# communication.net
KiCad netlist of a schematic drawn in EAGLE
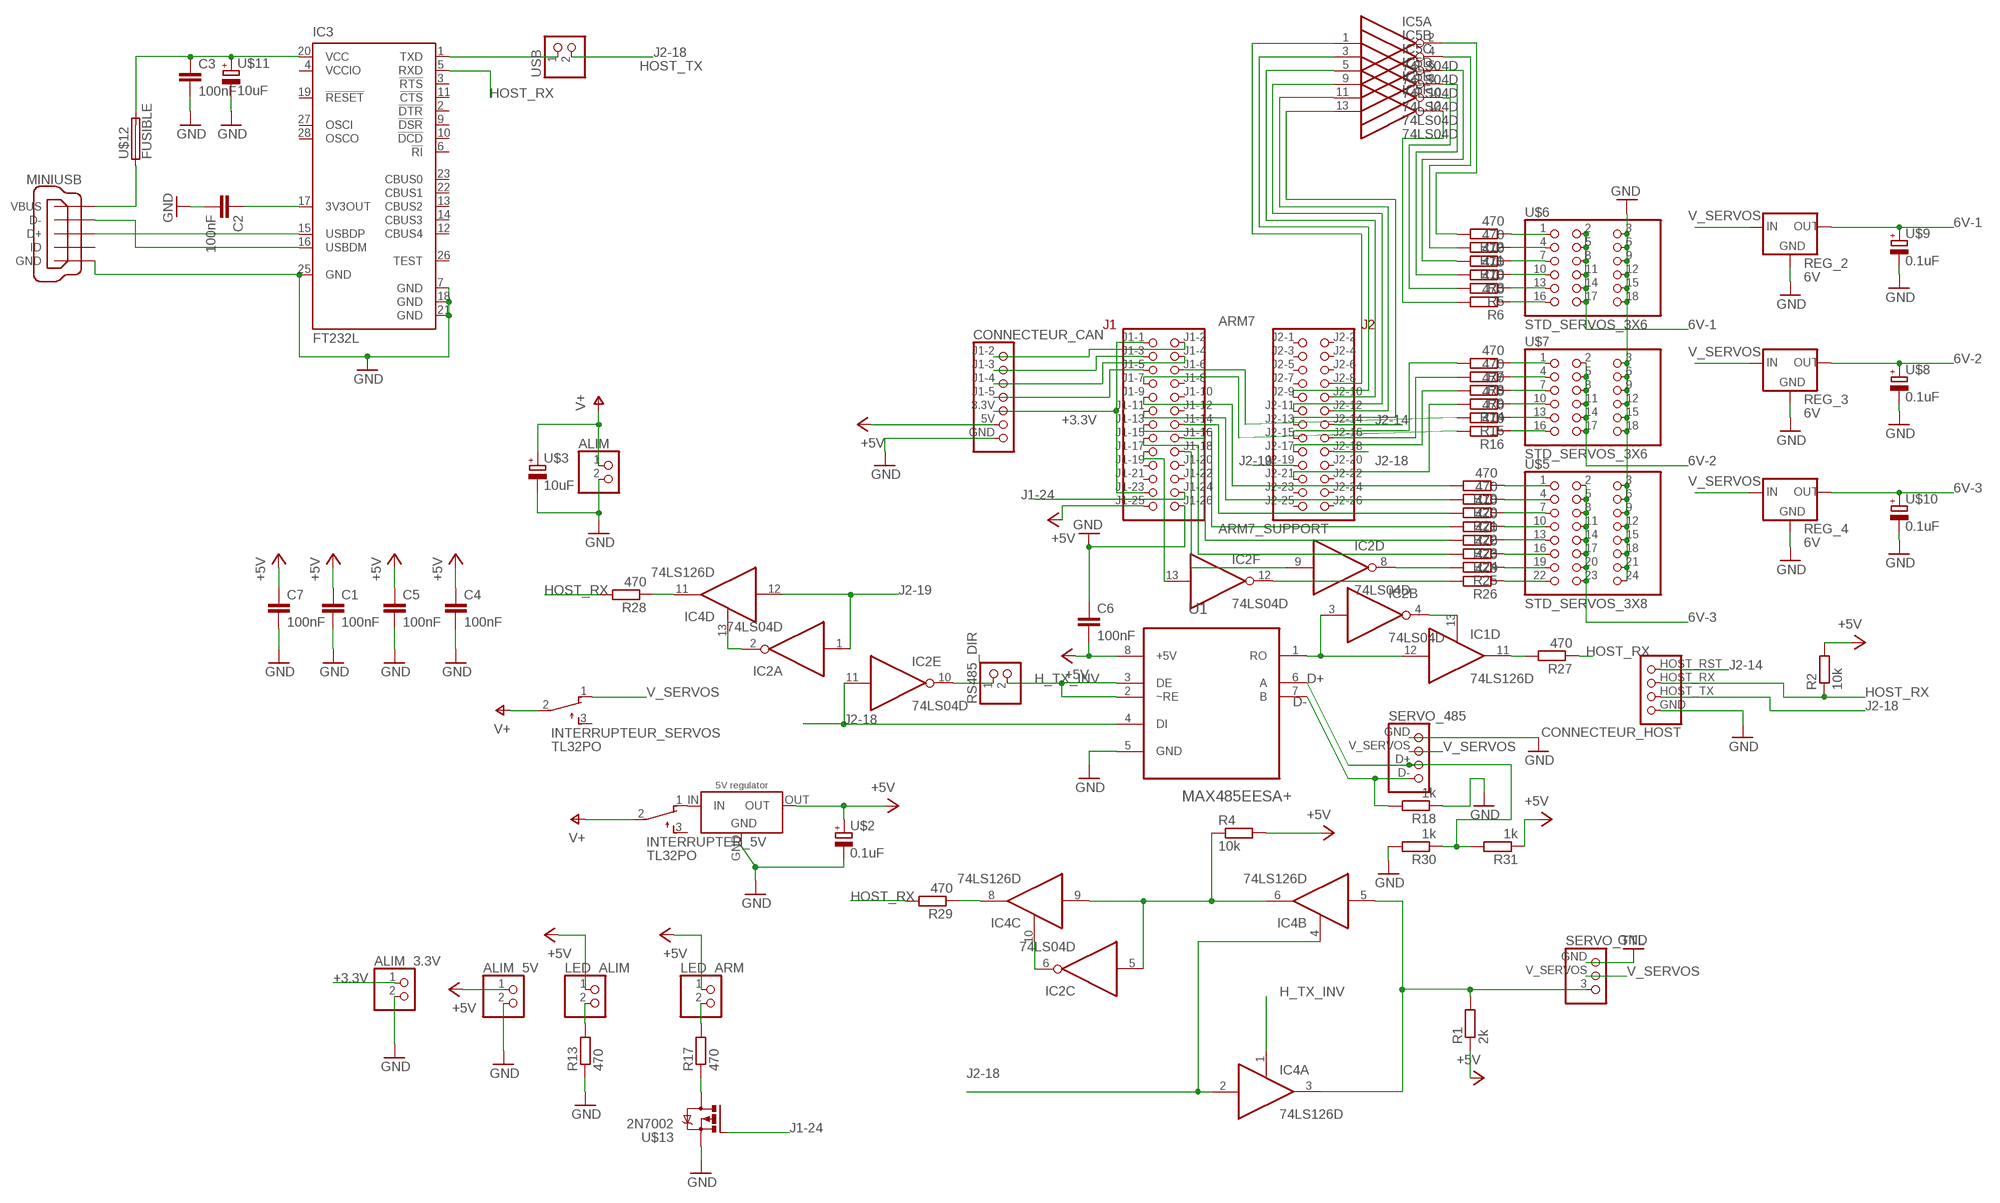
[diagram p0: schematic, sheet 1]

(export (version "E")
  (design (tool "Eeschema 10.0.6"))
  (components
    (comp (ref "ALIM")
      (value "CONNEC_1X02")
      (footprint "eagle-import:CONNEC_1X02")
      (libsource (lib "eagle-import") (part "CONNEC_1X02"))
    )
    (comp (ref "ALIM_3.3V")
      (value "CONNEC_1X02")
      (footprint "eagle-import:CONNEC_1X02")
      (libsource (lib "eagle-import") (part "CONNEC_1X02"))
    )
    (comp (ref "ALIM_5V")
      (value "CONNEC_1X02")
      (footprint "eagle-import:CONNEC_1X02")
      (libsource (lib "eagle-import") (part "CONNEC_1X02"))
    )
    (comp (ref "ARM7")
      (value "ARM7_SUPPORT")
      (footprint "eagle-import:ARM7_SUPPORT")
      (libsource (lib "eagle-import") (part "ARM7_SUPPORT"))
    )
    (comp (ref "C1")
      (value "100nF")
      (footprint "eagle-import:C1210")
      (libsource (lib "eagle-import") (part "C_EU_1210"))
    )
    (comp (ref "C2")
      (value "100nF")
      (footprint "eagle-import:C1210")
      (libsource (lib "eagle-import") (part "C_EU_1210"))
    )
    (comp (ref "C3")
      (value "100nF")
      (footprint "eagle-import:C1210")
      (libsource (lib "eagle-import") (part "C_EU_1210"))
    )
    (comp (ref "C4")
      (value "100nF")
      (footprint "eagle-import:C1210")
      (libsource (lib "eagle-import") (part "C_EU_1210"))
    )
    (comp (ref "C5")
      (value "100nF")
      (footprint "eagle-import:C1210")
      (libsource (lib "eagle-import") (part "C_EU_1210"))
    )
    (comp (ref "C6")
      (value "100nF")
      (footprint "eagle-import:C1210")
      (libsource (lib "eagle-import") (part "C_EU_1210"))
    )
    (comp (ref "C7")
      (value "100nF")
      (footprint "eagle-import:C1210")
      (libsource (lib "eagle-import") (part "C_EU_1210"))
    )
    (comp (ref "CONNECTEUR_CAN")
      (value "CONNECTEUR_CAN")
      (footprint "eagle-import:CONNECTEUR_CAN")
      (libsource (lib "eagle-import") (part "CONNECTEUR_CAN"))
    )
    (comp (ref "CONNECTEUR_HOST")
      (value "CONNECTEUR_HOST")
      (footprint "eagle-import:CONNECTEUR_HOST")
      (libsource (lib "eagle-import") (part "CONNECTEUR_HOST"))
    )
    (comp (ref "IC1")
      (value "74LS126D")
      (footprint "eagle-import:SO14")
      (libsource (lib "eagle-import") (part "74126DLS"))
    )
    (comp (ref "IC2")
      (value "74LS04D")
      (footprint "eagle-import:SO14")
      (libsource (lib "eagle-import") (part "7404DLS"))
    )
    (comp (ref "IC3")
      (value "FT232L")
      (footprint "eagle-import:SSOP28")
      (fields (field (name "MPN") "FT232RL"))
      (libsource (lib "eagle-import") (part "FT232L"))
    )
    (comp (ref "IC4")
      (value "74LS126D")
      (footprint "eagle-import:SO14")
      (libsource (lib "eagle-import") (part "74126DLS"))
    )
    (comp (ref "IC5")
      (value "74LS04D")
      (footprint "eagle-import:SO14")
      (libsource (lib "eagle-import") (part "7404DLS"))
    )
    (comp (ref "INTERRUPTER_5V")
      (value "TL32PO")
      (footprint "eagle-import:TL3XPO")
      (libsource (lib "eagle-import") (part "TL32PO"))
    )
    (comp (ref "INTERRUPTEUR_SERVOS")
      (value "TL32PO")
      (footprint "eagle-import:TL3XPO")
      (libsource (lib "eagle-import") (part "TL32PO"))
    )
    (comp (ref "LED_ALIM")
      (value "CONNEC_1X02")
      (footprint "eagle-import:CONNEC_1X02")
      (libsource (lib "eagle-import") (part "CONNEC_1X02"))
    )
    (comp (ref "LED_ARM")
      (value "CONNEC_1X02")
      (footprint "eagle-import:CONNEC_1X02")
      (libsource (lib "eagle-import") (part "CONNEC_1X02"))
    )
    (comp (ref "MINIUSB")
      (value "MINIUSB")
      (footprint "eagle-import:MINI_USB")
      (libsource (lib "eagle-import") (part "MINIUSB"))
    )
    (comp (ref "R1")
      (value "2k")
      (footprint "eagle-import:R0805")
      (libsource (lib "eagle-import") (part "R-EU_R0805"))
    )
    (comp (ref "R2")
      (value "10k")
      (footprint "eagle-import:R0805")
      (libsource (lib "eagle-import") (part "R-EU_R0805"))
    )
    (comp (ref "R3")
      (value "470")
      (footprint "eagle-import:R0805")
      (libsource (lib "eagle-import") (part "R-EU_R0805"))
    )
    (comp (ref "R4")
      (value "10k")
      (footprint "eagle-import:R0805")
      (libsource (lib "eagle-import") (part "R-EU_R0805"))
    )
    (comp (ref "R5")
      (value "470")
      (footprint "eagle-import:R0805")
      (libsource (lib "eagle-import") (part "R-EU_R0805"))
    )
    (comp (ref "R6")
      (value "470")
      (footprint "eagle-import:R0805")
      (libsource (lib "eagle-import") (part "R-EU_R0805"))
    )
    (comp (ref "R7")
      (value "470")
      (footprint "eagle-import:R0805")
      (libsource (lib "eagle-import") (part "R-EU_R0805"))
    )
    (comp (ref "R8")
      (value "470")
      (footprint "eagle-import:R0805")
      (libsource (lib "eagle-import") (part "R-EU_R0805"))
    )
    (comp (ref "R9")
      (value "470")
      (footprint "eagle-import:R0805")
      (libsource (lib "eagle-import") (part "R-EU_R0805"))
    )
    (comp (ref "R10")
      (value "470")
      (footprint "eagle-import:R0805")
      (libsource (lib "eagle-import") (part "R-EU_R0805"))
    )
    (comp (ref "R11")
      (value "470")
      (footprint "eagle-import:R0805")
      (libsource (lib "eagle-import") (part "R-EU_R0805"))
    )
    (comp (ref "R12")
      (value "470")
      (footprint "eagle-import:R0805")
      (libsource (lib "eagle-import") (part "R-EU_R0805"))
    )
    (comp (ref "R13")
      (value "470")
      (footprint "eagle-import:R0805")
      (libsource (lib "eagle-import") (part "R-EU_R0805"))
    )
    (comp (ref "R14")
      (value "470")
      (footprint "eagle-import:R0805")
      (libsource (lib "eagle-import") (part "R-EU_R0805"))
    )
    (comp (ref "R15")
      (value "470")
      (footprint "eagle-import:R0805")
      (libsource (lib "eagle-import") (part "R-EU_R0805"))
    )
    (comp (ref "R16")
      (value "470")
      (footprint "eagle-import:R0805")
      (libsource (lib "eagle-import") (part "R-EU_R0805"))
    )
    (comp (ref "R17")
      (value "470")
      (footprint "eagle-import:R0805")
      (libsource (lib "eagle-import") (part "R-EU_R0805"))
    )
    (comp (ref "R18")
      (value "1k")
      (footprint "eagle-import:R0805")
      (libsource (lib "eagle-import") (part "R-EU_R0805"))
    )
    (comp (ref "R19")
      (value "470")
      (footprint "eagle-import:R0805")
      (libsource (lib "eagle-import") (part "R-EU_R0805"))
    )
    (comp (ref "R20")
      (value "470")
      (footprint "eagle-import:R0805")
      (libsource (lib "eagle-import") (part "R-EU_R0805"))
    )
    (comp (ref "R21")
      (value "470")
      (footprint "eagle-import:R0805")
      (libsource (lib "eagle-import") (part "R-EU_R0805"))
    )
    (comp (ref "R22")
      (value "470")
      (footprint "eagle-import:R0805")
      (libsource (lib "eagle-import") (part "R-EU_R0805"))
    )
    (comp (ref "R23")
      (value "470")
      (footprint "eagle-import:R0805")
      (libsource (lib "eagle-import") (part "R-EU_R0805"))
    )
    (comp (ref "R24")
      (value "470")
      (footprint "eagle-import:R0805")
      (libsource (lib "eagle-import") (part "R-EU_R0805"))
    )
    (comp (ref "R25")
      (value "470")
      (footprint "eagle-import:R0805")
      (libsource (lib "eagle-import") (part "R-EU_R0805"))
    )
    (comp (ref "R26")
      (value "470")
      (footprint "eagle-import:R0805")
      (libsource (lib "eagle-import") (part "R-EU_R0805"))
    )
    (comp (ref "R27")
      (value "470")
      (footprint "eagle-import:R0805")
      (libsource (lib "eagle-import") (part "R-EU_R0805"))
    )
    (comp (ref "R28")
      (value "470")
      (footprint "eagle-import:R0805")
      (libsource (lib "eagle-import") (part "R-EU_R0805"))
    )
    (comp (ref "R29")
      (value "470")
      (footprint "eagle-import:R0805")
      (libsource (lib "eagle-import") (part "R-EU_R0805"))
    )
    (comp (ref "R30")
      (value "1k")
      (footprint "eagle-import:R0805")
      (libsource (lib "eagle-import") (part "R-EU_R0805"))
    )
    (comp (ref "R31")
      (value "1k")
      (footprint "eagle-import:R0805")
      (libsource (lib "eagle-import") (part "R-EU_R0805"))
    )
    (comp (ref "REG_2")
      (value "6V")
      (footprint "eagle-import:78XXL")
      (libsource (lib "eagle-import") (part "78XXL"))
    )
    (comp (ref "REG_3")
      (value "6V")
      (footprint "eagle-import:78XXL")
      (libsource (lib "eagle-import") (part "78XXL"))
    )
    (comp (ref "REG_4")
      (value "6V")
      (footprint "eagle-import:78XXL")
      (libsource (lib "eagle-import") (part "78XXL"))
    )
    (comp (ref "RS485_DIR")
      (value "CONNEC_1X02")
      (footprint "eagle-import:CONNEC_1X02")
      (libsource (lib "eagle-import") (part "CONNEC_1X02"))
    )
    (comp (ref "SERVO_485")
      (value "CONNECTEUR_485")
      (footprint "eagle-import:CONNECTEUR_485")
      (libsource (lib "eagle-import") (part "CONNECTEUR_485"))
    )
    (comp (ref "SERVO_TTL")
      (value "CONNECTEUR_TTL")
      (footprint "eagle-import:CONNECTEUR_TTL")
      (libsource (lib "eagle-import") (part "CONNECTEUR_TTL"))
    )
    (comp (ref "U$2")
      (value "0.1uF")
      (footprint "eagle-import:E2,5-6")
      (libsource (lib "eagle-import") (part "CPOL_EUCPOL_EU_2.54-6"))
    )
    (comp (ref "U$3")
      (value "10uF")
      (footprint "eagle-import:E5-10,5")
      (libsource (lib "eagle-import") (part "CPOL_EUCPOL_EU_5-10,5"))
    )
    (comp (ref "U$5")
      (value "STD_SERVOS_3X8")
      (footprint "eagle-import:STD_SERVOS_3X8")
      (libsource (lib "eagle-import") (part "STD_SERVOS_3X8"))
    )
    (comp (ref "U$6")
      (value "STD_SERVOS_3X6")
      (footprint "eagle-import:STD_SERVOS_3X6")
      (libsource (lib "eagle-import") (part "STD_SERVOS_3X6"))
    )
    (comp (ref "U$7")
      (value "STD_SERVOS_3X6")
      (footprint "eagle-import:STD_SERVOS_3X6")
      (libsource (lib "eagle-import") (part "STD_SERVOS_3X6"))
    )
    (comp (ref "U$8")
      (value "0.1uF")
      (footprint "eagle-import:E2,5-6")
      (libsource (lib "eagle-import") (part "CPOL_EUCPOL_EU_2.54-6"))
    )
    (comp (ref "U$9")
      (value "0.1uF")
      (footprint "eagle-import:E2,5-6")
      (libsource (lib "eagle-import") (part "CPOL_EUCPOL_EU_2.54-6"))
    )
    (comp (ref "U$10")
      (value "0.1uF")
      (footprint "eagle-import:E2,5-6")
      (libsource (lib "eagle-import") (part "CPOL_EUCPOL_EU_2.54-6"))
    )
    (comp (ref "U$11")
      (value "10uF")
      (footprint "eagle-import:E5-10,5")
      (libsource (lib "eagle-import") (part "CPOL_EUCPOL_EU_5-10,5"))
    )
    (comp (ref "U$12")
      (value "FUSIBLE")
      (footprint "eagle-import:FUSIBLE")
      (libsource (lib "eagle-import") (part "FUSIBLE"))
    )
    (comp (ref "U$13")
      (value "2N7002")
      (footprint "eagle-import:SOT23")
      (libsource (lib "eagle-import") (part "2N7002"))
    )
    (comp (ref "U$14")
      (value "5V regulator")
      (footprint "eagle-import:REGULATEUR_CMS")
      (libsource (lib "eagle-import") (part "REGULATEUR_CMS"))
    )
    (comp (ref "U1")
      (value "MAX485EESA+")
      (footprint "eagle-import:SOIC127P600X175-8N")
      (libsource (lib "eagle-import") (part "MAX485EESA+"))
    )
    (comp (ref "USB")
      (value "CONNEC_1X02")
      (footprint "eagle-import:CONNEC_1X02")
      (libsource (lib "eagle-import") (part "CONNEC_1X02"))
    )
  )
  (nets
    (net (code "1") (name "+5V") (class "Default")
      (node (ref "ALIM_5V") (pin "1") (pinfunction "1_1") (pintype "passive"))
      (node (ref "ARM7") (pin "J1-25") (pinfunction "25_J1-25") (pintype "passive"))
      (node (ref "C1") (pin "1") (pinfunction "1_1") (pintype "passive"))
      (node (ref "C4") (pin "1") (pinfunction "1_1") (pintype "passive"))
      (node (ref "C5") (pin "1") (pinfunction "1_1") (pintype "passive"))
      (node (ref "C6") (pin "2") (pinfunction "2_2") (pintype "passive"))
      (node (ref "C7") (pin "1") (pinfunction "1_1") (pintype "passive"))
      (node (ref "CONNECTEUR_CAN") (pin "5V") (pinfunction "5V_5V") (pintype "passive"))
      (node (ref "LED_ALIM") (pin "1") (pinfunction "1_1") (pintype "passive"))
      (node (ref "LED_ARM") (pin "1") (pinfunction "1_1") (pintype "passive"))
      (node (ref "R1") (pin "1") (pinfunction "1_1") (pintype "passive"))
      (node (ref "R2") (pin "2") (pinfunction "2_2") (pintype "passive"))
      (node (ref "R31") (pin "1") (pinfunction "1_1") (pintype "passive"))
      (node (ref "R4") (pin "2") (pinfunction "2_2") (pintype "passive"))
      (node (ref "U$14") (pin "OUT") (pinfunction "OUT_OUT") (pintype "output"))
      (node (ref "U$2") (pin "+") (pinfunction "+_+") (pintype "passive"))
      (node (ref "U1") (pin "8") (pinfunction "+5V_8") (pintype "power_in"))
    )
    (net (code "2") (name "/+3.3V") (class "Default")
      (node (ref "ALIM_3.3V") (pin "1") (pinfunction "1_1") (pintype "passive"))
      (node (ref "ARM7") (pin "J1-1") (pinfunction "1_J1-1") (pintype "passive"))
      (node (ref "ARM7") (pin "J1-23") (pinfunction "23_J1-23") (pintype "passive"))
      (node (ref "CONNECTEUR_CAN") (pin "3.3V") (pinfunction "3.3V_3.3V") (pintype "passive"))
    )
    (net (code "3") (name "/6V-1") (class "Default")
      (node (ref "REG_2") (pin "OUT") (pinfunction "OUT_OUT") (pintype "passive"))
      (node (ref "U$6") (pin "11") (pinfunction "11_11") (pintype "passive"))
      (node (ref "U$6") (pin "14") (pinfunction "14_14") (pintype "passive"))
      (node (ref "U$6") (pin "17") (pinfunction "17_17") (pintype "passive"))
      (node (ref "U$6") (pin "2") (pinfunction "2_2") (pintype "passive"))
      (node (ref "U$6") (pin "5") (pinfunction "5_5") (pintype "passive"))
      (node (ref "U$6") (pin "8") (pinfunction "8_8") (pintype "passive"))
      (node (ref "U$9") (pin "+") (pinfunction "+_+") (pintype "passive"))
    )
    (net (code "4") (name "/6V-2") (class "Default")
      (node (ref "REG_3") (pin "OUT") (pinfunction "OUT_OUT") (pintype "passive"))
      (node (ref "U$7") (pin "11") (pinfunction "11_11") (pintype "passive"))
      (node (ref "U$7") (pin "14") (pinfunction "14_14") (pintype "passive"))
      (node (ref "U$7") (pin "17") (pinfunction "17_17") (pintype "passive"))
      (node (ref "U$7") (pin "2") (pinfunction "2_2") (pintype "passive"))
      (node (ref "U$7") (pin "5") (pinfunction "5_5") (pintype "passive"))
      (node (ref "U$7") (pin "8") (pinfunction "8_8") (pintype "passive"))
      (node (ref "U$8") (pin "+") (pinfunction "+_+") (pintype "passive"))
    )
    (net (code "5") (name "/6V-3") (class "Default")
      (node (ref "REG_4") (pin "OUT") (pinfunction "OUT_OUT") (pintype "passive"))
      (node (ref "U$10") (pin "+") (pinfunction "+_+") (pintype "passive"))
      (node (ref "U$5") (pin "11") (pinfunction "11_11") (pintype "passive"))
      (node (ref "U$5") (pin "14") (pinfunction "14_14") (pintype "passive"))
      (node (ref "U$5") (pin "17") (pinfunction "17_17") (pintype "passive"))
      (node (ref "U$5") (pin "2") (pinfunction "2_2") (pintype "passive"))
      (node (ref "U$5") (pin "20") (pinfunction "20_20") (pintype "passive"))
      (node (ref "U$5") (pin "23") (pinfunction "23_23") (pintype "passive"))
      (node (ref "U$5") (pin "5") (pinfunction "5_5") (pintype "passive"))
      (node (ref "U$5") (pin "8") (pinfunction "8_8") (pintype "passive"))
    )
    (net (code "6") (name "/D+") (class "Default")
      (node (ref "R30") (pin "1") (pinfunction "1_1") (pintype "passive"))
      (node (ref "R31") (pin "2") (pinfunction "2_2") (pintype "passive"))
      (node (ref "SERVO_485") (pin "D+") (pinfunction "D+_D+") (pintype "passive"))
      (node (ref "U1") (pin "6") (pinfunction "A_6") (pintype "bidirectional"))
    )
    (net (code "7") (name "/D-") (class "Default")
      (node (ref "R18") (pin "2") (pinfunction "2_2") (pintype "passive"))
      (node (ref "SERVO_485") (pin "D-") (pinfunction "D-_D-") (pintype "passive"))
      (node (ref "U1") (pin "7") (pinfunction "B_7") (pintype "bidirectional"))
    )
    (net (code "8") (name "/HOST_RX") (class "Default")
      (node (ref "CONNECTEUR_HOST") (pin "HOST_RX") (pinfunction "HOST_RX_HOST_RX") (pintype "passive"))
      (node (ref "IC3") (pin "5") (pinfunction "RXD_5") (pintype "input"))
      (node (ref "R2") (pin "1") (pinfunction "1_1") (pintype "passive"))
      (node (ref "R27") (pin "1") (pinfunction "1_1") (pintype "passive"))
      (node (ref "R28") (pin "2") (pinfunction "2_2") (pintype "passive"))
      (node (ref "R29") (pin "2") (pinfunction "2_2") (pintype "passive"))
    )
    (net (code "9") (name "/H_TX_INV") (class "Default")
      (node (ref "IC4") (pin "1") (pinfunction "OE_1") (pintype "input"))
      (node (ref "RS485_DIR") (pin "2") (pinfunction "2_2") (pintype "passive"))
      (node (ref "U1") (pin "2") (pinfunction "~{RE}_2") (pintype "input"))
      (node (ref "U1") (pin "3") (pinfunction "DE_3") (pintype "input"))
    )
    (net (code "10") (name "/J1-24") (class "Default")
      (node (ref "ARM7") (pin "J1-24") (pinfunction "24_J1-24") (pintype "passive"))
      (node (ref "U$13") (pin "1") (pinfunction "G_1") (pintype "passive"))
    )
    (net (code "11") (name "/J2-14") (class "Default")
      (node (ref "ARM7") (pin "J2-14") (pinfunction "40_J2-14") (pintype "passive"))
      (node (ref "CONNECTEUR_HOST") (pin "HOST_RST") (pinfunction "HOST_RST_HOST_RST") (pintype "passive"))
    )
    (net (code "12") (name "/J2-18") (class "Default")
      (node (ref "ARM7") (pin "J2-18") (pinfunction "44_J2-18") (pintype "passive"))
      (node (ref "CONNECTEUR_HOST") (pin "HOST_TX") (pinfunction "HOST_TX_HOST_TX") (pintype "passive"))
      (node (ref "IC2") (pin "11") (pinfunction "I_11") (pintype "input"))
      (node (ref "IC4") (pin "2") (pinfunction "I_2") (pintype "input"))
      (node (ref "IC4") (pin "4") (pinfunction "OE_4") (pintype "input"))
      (node (ref "U1") (pin "4") (pinfunction "DI_4") (pintype "input"))
      (node (ref "USB") (pin "2") (pinfunction "2_2") (pintype "passive"))
    )
    (net (code "13") (name "/J2-19") (class "Default")
      (node (ref "ARM7") (pin "J2-19") (pinfunction "45_J2-19") (pintype "passive"))
      (node (ref "IC2") (pin "1") (pinfunction "I_1") (pintype "input"))
      (node (ref "IC4") (pin "12") (pinfunction "I_12") (pintype "input"))
    )
    (net (code "14") (name "/VCCIO") (class "Default")
      (node (ref "IC3") (pin "4") (pinfunction "VCCIO_4") (pintype "power_in"))
    )
    (net (code "15") (name "/V_SERVOS") (class "Default")
      (node (ref "INTERRUPTEUR_SERVOS") (pin "1") (pinfunction "O_1") (pintype "passive"))
      (node (ref "REG_2") (pin "IN") (pinfunction "IN_IN") (pintype "input"))
      (node (ref "REG_3") (pin "IN") (pinfunction "IN_IN") (pintype "input"))
      (node (ref "REG_4") (pin "IN") (pinfunction "IN_IN") (pintype "input"))
      (node (ref "SERVO_485") (pin "V_SERVOS") (pinfunction "V_SERVOS_V_SERVOS") (pintype "passive"))
      (node (ref "SERVO_TTL") (pin "V_SERVOS") (pinfunction "V_SERVOS_V_SERVOS") (pintype "passive"))
    )
    (net (code "16") (name "GND") (class "Default")
      (node (ref "ALIM") (pin "2") (pinfunction "2_2") (pintype "passive"))
      (node (ref "ALIM_3.3V") (pin "2") (pinfunction "2_2") (pintype "passive"))
      (node (ref "ALIM_5V") (pin "2") (pinfunction "2_2") (pintype "passive"))
      (node (ref "ARM7") (pin "J1-26") (pinfunction "26_J1-26") (pintype "passive"))
      (node (ref "C1") (pin "2") (pinfunction "2_2") (pintype "passive"))
      (node (ref "C2") (pin "2") (pinfunction "2_2") (pintype "passive"))
      (node (ref "C3") (pin "2") (pinfunction "2_2") (pintype "passive"))
      (node (ref "C4") (pin "2") (pinfunction "2_2") (pintype "passive"))
      (node (ref "C5") (pin "2") (pinfunction "2_2") (pintype "passive"))
      (node (ref "C6") (pin "1") (pinfunction "1_1") (pintype "passive"))
      (node (ref "C7") (pin "2") (pinfunction "2_2") (pintype "passive"))
      (node (ref "CONNECTEUR_CAN") (pin "GND") (pinfunction "GND_GND") (pintype "passive"))
      (node (ref "CONNECTEUR_HOST") (pin "GND") (pinfunction "GND_GND") (pintype "passive"))
      (node (ref "IC3") (pin "18") (pinfunction "GND_18") (pintype "power_in"))
      (node (ref "IC3") (pin "21") (pinfunction "GND_21") (pintype "power_in"))
      (node (ref "IC3") (pin "25") (pinfunction "GND_25") (pintype "power_in"))
      (node (ref "IC3") (pin "7") (pinfunction "GND_7") (pintype "power_in"))
      (node (ref "MINIUSB") (pin "GND") (pinfunction "GND_GND") (pintype "passive"))
      (node (ref "R13") (pin "1") (pinfunction "1_1") (pintype "passive"))
      (node (ref "R18") (pin "1") (pinfunction "1_1") (pintype "passive"))
      (node (ref "R30") (pin "2") (pinfunction "2_2") (pintype "passive"))
      (node (ref "REG_2") (pin "GND") (pinfunction "GND_GND") (pintype "input"))
      (node (ref "REG_3") (pin "GND") (pinfunction "GND_GND") (pintype "input"))
      (node (ref "REG_4") (pin "GND") (pinfunction "GND_GND") (pintype "input"))
      (node (ref "SERVO_485") (pin "GND") (pinfunction "GND_GND") (pintype "passive"))
      (node (ref "SERVO_TTL") (pin "GND") (pinfunction "GND_GND") (pintype "passive"))
      (node (ref "U$10") (pin "-") (pinfunction "-_-") (pintype "passive"))
      (node (ref "U$11") (pin "-") (pinfunction "-_-") (pintype "passive"))
      (node (ref "U$13") (pin "2") (pinfunction "S_2") (pintype "passive"))
      (node (ref "U$14") (pin "GND") (pinfunction "GND_GND") (pintype "power_in"))
      (node (ref "U$2") (pin "-") (pinfunction "-_-") (pintype "passive"))
      (node (ref "U$3") (pin "-") (pinfunction "-_-") (pintype "passive"))
      (node (ref "U$5") (pin "12") (pinfunction "12_12") (pintype "passive"))
      (node (ref "U$5") (pin "15") (pinfunction "15_15") (pintype "passive"))
      (node (ref "U$5") (pin "18") (pinfunction "18_18") (pintype "passive"))
      (node (ref "U$5") (pin "21") (pinfunction "21_21") (pintype "passive"))
      (node (ref "U$5") (pin "24") (pinfunction "24_24") (pintype "passive"))
      (node (ref "U$5") (pin "3") (pinfunction "3_3") (pintype "passive"))
      (node (ref "U$5") (pin "6") (pinfunction "6_6") (pintype "passive"))
      (node (ref "U$5") (pin "9") (pinfunction "9_9") (pintype "passive"))
      (node (ref "U$6") (pin "12") (pinfunction "12_12") (pintype "passive"))
      (node (ref "U$6") (pin "15") (pinfunction "15_15") (pintype "passive"))
      (node (ref "U$6") (pin "18") (pinfunction "18_18") (pintype "passive"))
      (node (ref "U$6") (pin "3") (pinfunction "3_3") (pintype "passive"))
      (node (ref "U$6") (pin "6") (pinfunction "6_6") (pintype "passive"))
      (node (ref "U$6") (pin "9") (pinfunction "9_9") (pintype "passive"))
      (node (ref "U$7") (pin "12") (pinfunction "12_12") (pintype "passive"))
      (node (ref "U$7") (pin "15") (pinfunction "15_15") (pintype "passive"))
      (node (ref "U$7") (pin "18") (pinfunction "18_18") (pintype "passive"))
      (node (ref "U$7") (pin "3") (pinfunction "3_3") (pintype "passive"))
      (node (ref "U$7") (pin "6") (pinfunction "6_6") (pintype "passive"))
      (node (ref "U$7") (pin "9") (pinfunction "9_9") (pintype "passive"))
      (node (ref "U$8") (pin "-") (pinfunction "-_-") (pintype "passive"))
      (node (ref "U$9") (pin "-") (pinfunction "-_-") (pintype "passive"))
      (node (ref "U1") (pin "5") (pinfunction "GND_5") (pintype "passive"))
    )
    (net (code "17") (name "Net-(ARM7-2)") (class "Default")
      (node (ref "ARM7") (pin "J1-2") (pinfunction "2_J1-2") (pintype "passive"))
      (node (ref "CONNECTEUR_CAN") (pin "J1-2") (pinfunction "J1-2_J1-2") (pintype "passive"))
    )
    (net (code "18") (name "Net-(ARM7-3)") (class "Default")
      (node (ref "ARM7") (pin "J1-3") (pinfunction "3_J1-3") (pintype "passive"))
      (node (ref "CONNECTEUR_CAN") (pin "J1-3") (pinfunction "J1-3_J1-3") (pintype "passive"))
    )
    (net (code "19") (name "Net-(ARM7-4)") (class "Default")
      (node (ref "ARM7") (pin "J1-4") (pinfunction "4_J1-4") (pintype "passive"))
      (node (ref "CONNECTEUR_CAN") (pin "J1-4") (pinfunction "J1-4_J1-4") (pintype "passive"))
    )
    (net (code "20") (name "Net-(ARM7-5)") (class "Default")
      (node (ref "ARM7") (pin "J1-5") (pinfunction "5_J1-5") (pintype "passive"))
      (node (ref "CONNECTEUR_CAN") (pin "J1-5") (pinfunction "J1-5_J1-5") (pintype "passive"))
    )
    (net (code "21") (name "Net-(ARM7-6)") (class "Default")
      (node (ref "ARM7") (pin "J1-6") (pinfunction "6_J1-6") (pintype "passive"))
      (node (ref "R15") (pin "2") (pinfunction "2_2") (pintype "passive"))
    )
    (net (code "22") (name "Net-(ARM7-7)") (class "Default")
      (node (ref "ARM7") (pin "J1-7") (pinfunction "7_J1-7") (pintype "passive"))
      (node (ref "R16") (pin "2") (pinfunction "2_2") (pintype "passive"))
    )
    (net (code "23") (name "Net-(ARM7-9)") (class "Default")
      (node (ref "ARM7") (pin "J1-9") (pinfunction "9_J1-9") (pintype "passive"))
      (node (ref "R19") (pin "2") (pinfunction "2_2") (pintype "passive"))
    )
    (net (code "24") (name "Net-(ARM7-11)") (class "Default")
      (node (ref "ARM7") (pin "J1-11") (pinfunction "11_J1-11") (pintype "passive"))
      (node (ref "R20") (pin "2") (pinfunction "2_2") (pintype "passive"))
    )
    (net (code "25") (name "Net-(ARM7-13)") (class "Default")
      (node (ref "ARM7") (pin "J1-13") (pinfunction "13_J1-13") (pintype "passive"))
      (node (ref "R22") (pin "2") (pinfunction "2_2") (pintype "passive"))
    )
    (net (code "26") (name "Net-(ARM7-14)") (class "Default")
      (node (ref "ARM7") (pin "J1-14") (pinfunction "14_J1-14") (pintype "passive"))
      (node (ref "R21") (pin "2") (pinfunction "2_2") (pintype "passive"))
    )
    (net (code "27") (name "Net-(ARM7-15)") (class "Default")
      (node (ref "ARM7") (pin "J1-15") (pinfunction "15_J1-15") (pintype "passive"))
      (node (ref "R24") (pin "2") (pinfunction "2_2") (pintype "passive"))
    )
    (net (code "28") (name "Net-(ARM7-16)") (class "Default")
      (node (ref "ARM7") (pin "J1-16") (pinfunction "16_J1-16") (pintype "passive"))
      (node (ref "R23") (pin "2") (pinfunction "2_2") (pintype "passive"))
    )
    (net (code "29") (name "Net-(ARM7-17)") (class "Default")
      (node (ref "ARM7") (pin "J1-17") (pinfunction "17_J1-17") (pintype "passive"))
      (node (ref "IC2") (pin "13") (pinfunction "I_13") (pintype "input"))
    )
    (net (code "30") (name "Net-(ARM7-18)") (class "Default")
      (node (ref "ARM7") (pin "J1-18") (pinfunction "18_J1-18") (pintype "passive"))
      (node (ref "IC2") (pin "9") (pinfunction "I_9") (pintype "input"))
    )
    (net (code "31") (name "Net-(ARM7-34)") (class "Default")
      (node (ref "ARM7") (pin "J2-8") (pinfunction "34_J2-8") (pintype "passive"))
      (node (ref "IC5") (pin "1") (pinfunction "I_1") (pintype "input"))
    )
    (net (code "32") (name "Net-(ARM7-35)") (class "Default")
      (node (ref "ARM7") (pin "J2-9") (pinfunction "35_J2-9") (pintype "passive"))
      (node (ref "IC5") (pin "3") (pinfunction "I_3") (pintype "input"))
    )
    (net (code "33") (name "Net-(ARM7-36)") (class "Default")
      (node (ref "ARM7") (pin "J2-10") (pinfunction "36_J2-10") (pintype "passive"))
      (node (ref "IC5") (pin "5") (pinfunction "I_5") (pintype "input"))
    )
    (net (code "34") (name "Net-(ARM7-37)") (class "Default")
      (node (ref "ARM7") (pin "J2-11") (pinfunction "37_J2-11") (pintype "passive"))
      (node (ref "IC5") (pin "9") (pinfunction "I_9") (pintype "input"))
    )
    (net (code "35") (name "Net-(ARM7-38)") (class "Default")
      (node (ref "ARM7") (pin "J2-12") (pinfunction "38_J2-12") (pintype "passive"))
      (node (ref "IC5") (pin "11") (pinfunction "I_11") (pintype "input"))
    )
    (net (code "36") (name "Net-(ARM7-39)") (class "Default")
      (node (ref "ARM7") (pin "J2-13") (pinfunction "39_J2-13") (pintype "passive"))
      (node (ref "IC5") (pin "13") (pinfunction "I_13") (pintype "input"))
    )
    (net (code "37") (name "Net-(ARM7-41)") (class "Default")
      (node (ref "ARM7") (pin "J2-15") (pinfunction "41_J2-15") (pintype "passive"))
      (node (ref "R7") (pin "2") (pinfunction "2_2") (pintype "passive"))
    )
    (net (code "38") (name "Net-(ARM7-42)") (class "Default")
      (node (ref "ARM7") (pin "J2-16") (pinfunction "42_J2-16") (pintype "passive"))
      (node (ref "R8") (pin "2") (pinfunction "2_2") (pintype "passive"))
    )
    (net (code "39") (name "Net-(ARM7-43)") (class "Default")
      (node (ref "ARM7") (pin "J2-17") (pinfunction "43_J2-17") (pintype "passive"))
      (node (ref "R9") (pin "2") (pinfunction "2_2") (pintype "passive"))
    )
    (net (code "40") (name "Net-(ARM7-47)") (class "Default")
      (node (ref "ARM7") (pin "J2-21") (pinfunction "47_J2-21") (pintype "passive"))
      (node (ref "R14") (pin "2") (pinfunction "2_2") (pintype "passive"))
    )
    (net (code "41") (name "Net-(IC1D-I)") (class "Default")
      (node (ref "IC1") (pin "12") (pinfunction "I_12") (pintype "input"))
      (node (ref "IC2") (pin "3") (pinfunction "I_3") (pintype "input"))
      (node (ref "U1") (pin "1") (pinfunction "RO_1") (pintype "output"))
    )
    (net (code "42") (name "Net-(IC1D-O)") (class "Default")
      (node (ref "IC1") (pin "11") (pinfunction "O_11") (pintype "output"))
      (node (ref "R27") (pin "2") (pinfunction "2_2") (pintype "passive"))
    )
    (net (code "43") (name "Net-(IC1D-OE)") (class "Default")
      (node (ref "IC1") (pin "13") (pinfunction "OE_13") (pintype "input"))
      (node (ref "IC2") (pin "4") (pinfunction "O_4") (pintype "output"))
    )
    (net (code "44") (name "Net-(IC2A-O)") (class "Default")
      (node (ref "IC2") (pin "2") (pinfunction "O_2") (pintype "output"))
      (node (ref "IC4") (pin "13") (pinfunction "OE_13") (pintype "input"))
    )
    (net (code "45") (name "Net-(IC2C-I)") (class "Default")
      (node (ref "IC2") (pin "5") (pinfunction "I_5") (pintype "input"))
      (node (ref "IC4") (pin "6") (pinfunction "O_6") (pintype "output"))
      (node (ref "IC4") (pin "9") (pinfunction "I_9") (pintype "input"))
      (node (ref "R4") (pin "1") (pinfunction "1_1") (pintype "passive"))
    )
    (net (code "46") (name "Net-(IC2C-O)") (class "Default")
      (node (ref "IC2") (pin "6") (pinfunction "O_6") (pintype "output"))
      (node (ref "IC4") (pin "10") (pinfunction "OE_10") (pintype "input"))
    )
    (net (code "47") (name "Net-(IC2D-O)") (class "Default")
      (node (ref "IC2") (pin "8") (pinfunction "O_8") (pintype "output"))
      (node (ref "R25") (pin "2") (pinfunction "2_2") (pintype "passive"))
    )
    (net (code "48") (name "Net-(IC2E-O)") (class "Default")
      (node (ref "IC2") (pin "10") (pinfunction "O_10") (pintype "output"))
      (node (ref "RS485_DIR") (pin "1") (pinfunction "1_1") (pintype "passive"))
    )
    (net (code "49") (name "Net-(IC2F-O)") (class "Default")
      (node (ref "IC2") (pin "12") (pinfunction "O_12") (pintype "output"))
      (node (ref "R26") (pin "2") (pinfunction "2_2") (pintype "passive"))
    )
    (net (code "50") (name "Net-(IC3-3V3OUT)") (class "Default")
      (node (ref "C2") (pin "1") (pinfunction "1_1") (pintype "passive"))
      (node (ref "IC3") (pin "17") (pinfunction "3V3OUT_17") (pintype "output"))
    )
    (net (code "51") (name "Net-(IC3-TXD)") (class "Default")
      (node (ref "IC3") (pin "1") (pinfunction "TXD_1") (pintype "output"))
      (node (ref "USB") (pin "1") (pinfunction "1_1") (pintype "passive"))
    )
    (net (code "52") (name "Net-(IC3-USBDM)") (class "Default")
      (node (ref "IC3") (pin "16") (pinfunction "USBDM_16") (pintype "bidirectional"))
      (node (ref "MINIUSB") (pin "D-") (pinfunction "D-_D-") (pintype "passive"))
    )
    (net (code "53") (name "Net-(IC3-USBDP)") (class "Default")
      (node (ref "IC3") (pin "15") (pinfunction "USBDP_15") (pintype "bidirectional"))
      (node (ref "MINIUSB") (pin "D+") (pinfunction "D+_D+") (pintype "passive"))
    )
    (net (code "54") (name "Net-(IC3-VCC)") (class "Default")
      (node (ref "C3") (pin "1") (pinfunction "1_1") (pintype "passive"))
      (node (ref "IC3") (pin "20") (pinfunction "VCC_20") (pintype "power_in"))
      (node (ref "U$11") (pin "+") (pinfunction "+_+") (pintype "passive"))
      (node (ref "U$12") (pin "P$2") (pinfunction "2_P$2") (pintype "passive"))
    )
    (net (code "55") (name "Net-(IC4A-O)") (class "Default")
      (node (ref "IC4") (pin "3") (pinfunction "O_3") (pintype "output"))
      (node (ref "IC4") (pin "5") (pinfunction "I_5") (pintype "input"))
      (node (ref "R1") (pin "2") (pinfunction "2_2") (pintype "passive"))
      (node (ref "SERVO_TTL") (pin "3") (pinfunction "3_3") (pintype "passive"))
    )
    (net (code "56") (name "Net-(IC4C-O)") (class "Default")
      (node (ref "IC4") (pin "8") (pinfunction "O_8") (pintype "output"))
      (node (ref "R29") (pin "1") (pinfunction "1_1") (pintype "passive"))
    )
    (net (code "57") (name "Net-(IC4D-O)") (class "Default")
      (node (ref "IC4") (pin "11") (pinfunction "O_11") (pintype "output"))
      (node (ref "R28") (pin "1") (pinfunction "1_1") (pintype "passive"))
    )
    (net (code "58") (name "Net-(IC5A-O)") (class "Default")
      (node (ref "IC5") (pin "2") (pinfunction "O_2") (pintype "output"))
      (node (ref "R12") (pin "2") (pinfunction "2_2") (pintype "passive"))
    )
    (net (code "59") (name "Net-(IC5B-O)") (class "Default")
      (node (ref "IC5") (pin "4") (pinfunction "O_4") (pintype "output"))
      (node (ref "R11") (pin "2") (pinfunction "2_2") (pintype "passive"))
    )
    (net (code "60") (name "Net-(IC5C-O)") (class "Default")
      (node (ref "IC5") (pin "6") (pinfunction "O_6") (pintype "output"))
      (node (ref "R10") (pin "2") (pinfunction "2_2") (pintype "passive"))
    )
    (net (code "61") (name "Net-(IC5D-O)") (class "Default")
      (node (ref "IC5") (pin "8") (pinfunction "O_8") (pintype "output"))
      (node (ref "R3") (pin "2") (pinfunction "2_2") (pintype "passive"))
    )
    (net (code "62") (name "Net-(IC5E-O)") (class "Default")
      (node (ref "IC5") (pin "10") (pinfunction "O_10") (pintype "output"))
      (node (ref "R5") (pin "2") (pinfunction "2_2") (pintype "passive"))
    )
    (net (code "63") (name "Net-(IC5F-O)") (class "Default")
      (node (ref "IC5") (pin "12") (pinfunction "O_12") (pintype "output"))
      (node (ref "R6") (pin "2") (pinfunction "2_2") (pintype "passive"))
    )
    (net (code "64") (name "Net-(INTERRUPTER_5V-O)") (class "Default")
      (node (ref "INTERRUPTER_5V") (pin "1") (pinfunction "O_1") (pintype "passive"))
      (node (ref "U$14") (pin "IN") (pinfunction "IN_IN") (pintype "input"))
    )
    (net (code "65") (name "Net-(LED_ALIM-Pad2)") (class "Default")
      (node (ref "LED_ALIM") (pin "2") (pinfunction "2_2") (pintype "passive"))
      (node (ref "R13") (pin "2") (pinfunction "2_2") (pintype "passive"))
    )
    (net (code "66") (name "Net-(LED_ARM-Pad2)") (class "Default")
      (node (ref "LED_ARM") (pin "2") (pinfunction "2_2") (pintype "passive"))
      (node (ref "R17") (pin "2") (pinfunction "2_2") (pintype "passive"))
    )
    (net (code "67") (name "Net-(R3-Pad1)") (class "Default")
      (node (ref "R3") (pin "1") (pinfunction "1_1") (pintype "passive"))
      (node (ref "U$6") (pin "10") (pinfunction "10_10") (pintype "passive"))
    )
    (net (code "68") (name "Net-(R5-Pad1)") (class "Default")
      (node (ref "R5") (pin "1") (pinfunction "1_1") (pintype "passive"))
      (node (ref "U$6") (pin "13") (pinfunction "13_13") (pintype "passive"))
    )
    (net (code "69") (name "Net-(R6-Pad1)") (class "Default")
      (node (ref "R6") (pin "1") (pinfunction "1_1") (pintype "passive"))
      (node (ref "U$6") (pin "16") (pinfunction "16_16") (pintype "passive"))
    )
    (net (code "70") (name "Net-(R7-Pad1)") (class "Default")
      (node (ref "R7") (pin "1") (pinfunction "1_1") (pintype "passive"))
      (node (ref "U$7") (pin "1") (pinfunction "1_1") (pintype "passive"))
    )
    (net (code "71") (name "Net-(R8-Pad1)") (class "Default")
      (node (ref "R8") (pin "1") (pinfunction "1_1") (pintype "passive"))
      (node (ref "U$7") (pin "4") (pinfunction "4_4") (pintype "passive"))
    )
    (net (code "72") (name "Net-(R9-Pad1)") (class "Default")
      (node (ref "R9") (pin "1") (pinfunction "1_1") (pintype "passive"))
      (node (ref "U$7") (pin "7") (pinfunction "7_7") (pintype "passive"))
    )
    (net (code "73") (name "Net-(R10-Pad1)") (class "Default")
      (node (ref "R10") (pin "1") (pinfunction "1_1") (pintype "passive"))
      (node (ref "U$6") (pin "7") (pinfunction "7_7") (pintype "passive"))
    )
    (net (code "74") (name "Net-(R11-Pad1)") (class "Default")
      (node (ref "R11") (pin "1") (pinfunction "1_1") (pintype "passive"))
      (node (ref "U$6") (pin "4") (pinfunction "4_4") (pintype "passive"))
    )
    (net (code "75") (name "Net-(R12-Pad1)") (class "Default")
      (node (ref "R12") (pin "1") (pinfunction "1_1") (pintype "passive"))
      (node (ref "U$6") (pin "1") (pinfunction "1_1") (pintype "passive"))
    )
    (net (code "76") (name "Net-(R14-Pad1)") (class "Default")
      (node (ref "R14") (pin "1") (pinfunction "1_1") (pintype "passive"))
      (node (ref "U$7") (pin "10") (pinfunction "10_10") (pintype "passive"))
    )
    (net (code "77") (name "Net-(R15-Pad1)") (class "Default")
      (node (ref "R15") (pin "1") (pinfunction "1_1") (pintype "passive"))
      (node (ref "U$7") (pin "13") (pinfunction "13_13") (pintype "passive"))
    )
    (net (code "78") (name "Net-(R16-Pad1)") (class "Default")
      (node (ref "R16") (pin "1") (pinfunction "1_1") (pintype "passive"))
      (node (ref "U$7") (pin "16") (pinfunction "16_16") (pintype "passive"))
    )
    (net (code "79") (name "Net-(R19-Pad1)") (class "Default")
      (node (ref "R19") (pin "1") (pinfunction "1_1") (pintype "passive"))
      (node (ref "U$5") (pin "1") (pinfunction "1_1") (pintype "passive"))
    )
    (net (code "80") (name "Net-(R20-Pad1)") (class "Default")
      (node (ref "R20") (pin "1") (pinfunction "1_1") (pintype "passive"))
      (node (ref "U$5") (pin "4") (pinfunction "4_4") (pintype "passive"))
    )
    (net (code "81") (name "Net-(R21-Pad1)") (class "Default")
      (node (ref "R21") (pin "1") (pinfunction "1_1") (pintype "passive"))
      (node (ref "U$5") (pin "7") (pinfunction "7_7") (pintype "passive"))
    )
    (net (code "82") (name "Net-(R22-Pad1)") (class "Default")
      (node (ref "R22") (pin "1") (pinfunction "1_1") (pintype "passive"))
      (node (ref "U$5") (pin "10") (pinfunction "10_10") (pintype "passive"))
    )
    (net (code "83") (name "Net-(R23-Pad1)") (class "Default")
      (node (ref "R23") (pin "1") (pinfunction "1_1") (pintype "passive"))
      (node (ref "U$5") (pin "13") (pinfunction "13_13") (pintype "passive"))
    )
    (net (code "84") (name "Net-(R24-Pad1)") (class "Default")
      (node (ref "R24") (pin "1") (pinfunction "1_1") (pintype "passive"))
      (node (ref "U$5") (pin "16") (pinfunction "16_16") (pintype "passive"))
    )
    (net (code "85") (name "Net-(R25-Pad1)") (class "Default")
      (node (ref "R25") (pin "1") (pinfunction "1_1") (pintype "passive"))
      (node (ref "U$5") (pin "19") (pinfunction "19_19") (pintype "passive"))
    )
    (net (code "86") (name "Net-(R26-Pad1)") (class "Default")
      (node (ref "R26") (pin "1") (pinfunction "1_1") (pintype "passive"))
      (node (ref "U$5") (pin "22") (pinfunction "22_22") (pintype "passive"))
    )
    (net (code "87") (name "Net-(U$12-1)") (class "Default")
      (node (ref "MINIUSB") (pin "VBUS") (pinfunction "VBUS_VBUS") (pintype "passive"))
      (node (ref "U$12") (pin "P$1") (pinfunction "1_P$1") (pintype "passive"))
    )
    (net (code "88") (name "Net-(U$13-D)") (class "Default")
      (node (ref "R17") (pin "1") (pinfunction "1_1") (pintype "passive"))
      (node (ref "U$13") (pin "3") (pinfunction "D_3") (pintype "passive"))
    )
    (net (code "89") (name "V+") (class "Default")
      (node (ref "ALIM") (pin "1") (pinfunction "1_1") (pintype "passive"))
      (node (ref "INTERRUPTER_5V") (pin "2") (pinfunction "P_2") (pintype "passive"))
      (node (ref "INTERRUPTEUR_SERVOS") (pin "2") (pinfunction "P_2") (pintype "passive"))
      (node (ref "U$3") (pin "+") (pinfunction "+_+") (pintype "passive"))
    )
    (net (code "90") (name "unconnected-(ARM7-8-PadJ1-8)") (class "Default")
      (node (ref "ARM7") (pin "J1-8") (pinfunction "8_J1-8") (pintype "passive"))
    )
    (net (code "91") (name "unconnected-(ARM7-10-PadJ1-10)") (class "Default")
      (node (ref "ARM7") (pin "J1-10") (pinfunction "10_J1-10") (pintype "passive"))
    )
    (net (code "92") (name "unconnected-(ARM7-12-PadJ1-12)") (class "Default")
      (node (ref "ARM7") (pin "J1-12") (pinfunction "12_J1-12") (pintype "passive"))
    )
    (net (code "93") (name "unconnected-(ARM7-19-PadJ1-19)") (class "Default")
      (node (ref "ARM7") (pin "J1-19") (pinfunction "19_J1-19") (pintype "passive"))
    )
    (net (code "94") (name "unconnected-(ARM7-20-PadJ1-20)") (class "Default")
      (node (ref "ARM7") (pin "J1-20") (pinfunction "20_J1-20") (pintype "passive"))
    )
    (net (code "95") (name "unconnected-(ARM7-21-PadJ1-21)") (class "Default")
      (node (ref "ARM7") (pin "J1-21") (pinfunction "21_J1-21") (pintype "passive"))
    )
    (net (code "96") (name "unconnected-(ARM7-22-PadJ1-22)") (class "Default")
      (node (ref "ARM7") (pin "J1-22") (pinfunction "22_J1-22") (pintype "passive"))
    )
    (net (code "97") (name "unconnected-(ARM7-27-PadJ2-1)") (class "Default")
      (node (ref "ARM7") (pin "J2-1") (pinfunction "27_J2-1") (pintype "passive"))
    )
    (net (code "98") (name "unconnected-(ARM7-28-PadJ2-2)") (class "Default")
      (node (ref "ARM7") (pin "J2-2") (pinfunction "28_J2-2") (pintype "passive"))
    )
    (net (code "99") (name "unconnected-(ARM7-29-PadJ2-3)") (class "Default")
      (node (ref "ARM7") (pin "J2-3") (pinfunction "29_J2-3") (pintype "passive"))
    )
    (net (code "100") (name "unconnected-(ARM7-30-PadJ2-4)") (class "Default")
      (node (ref "ARM7") (pin "J2-4") (pinfunction "30_J2-4") (pintype "passive"))
    )
    (net (code "101") (name "unconnected-(ARM7-31-PadJ2-5)") (class "Default")
      (node (ref "ARM7") (pin "J2-5") (pinfunction "31_J2-5") (pintype "passive"))
    )
    (net (code "102") (name "unconnected-(ARM7-32-PadJ2-6)") (class "Default")
      (node (ref "ARM7") (pin "J2-6") (pinfunction "32_J2-6") (pintype "passive"))
    )
    (net (code "103") (name "unconnected-(ARM7-33-PadJ2-7)") (class "Default")
      (node (ref "ARM7") (pin "J2-7") (pinfunction "33_J2-7") (pintype "passive"))
    )
    (net (code "104") (name "unconnected-(ARM7-46-PadJ2-20)") (class "Default")
      (node (ref "ARM7") (pin "J2-20") (pinfunction "46_J2-20") (pintype "passive"))
    )
    (net (code "105") (name "unconnected-(ARM7-48-PadJ2-22)") (class "Default")
      (node (ref "ARM7") (pin "J2-22") (pinfunction "48_J2-22") (pintype "passive"))
    )
    (net (code "106") (name "unconnected-(ARM7-49-PadJ2-23)") (class "Default")
      (node (ref "ARM7") (pin "J2-23") (pinfunction "49_J2-23") (pintype "passive"))
    )
    (net (code "107") (name "unconnected-(ARM7-50-PadJ2-24)") (class "Default")
      (node (ref "ARM7") (pin "J2-24") (pinfunction "50_J2-24") (pintype "passive"))
    )
    (net (code "108") (name "unconnected-(ARM7-51-PadJ2-25)") (class "Default")
      (node (ref "ARM7") (pin "J2-25") (pinfunction "51_J2-25") (pintype "passive"))
    )
    (net (code "109") (name "unconnected-(ARM7-52-PadJ2-26)") (class "Default")
      (node (ref "ARM7") (pin "J2-26") (pinfunction "52_J2-26") (pintype "passive"))
    )
    (net (code "110") (name "unconnected-(IC3-CBUS0-Pad23)") (class "Default")
      (node (ref "IC3") (pin "23") (pinfunction "CBUS0_23") (pintype "bidirectional"))
    )
    (net (code "111") (name "unconnected-(IC3-CBUS1-Pad22)") (class "Default")
      (node (ref "IC3") (pin "22") (pinfunction "CBUS1_22") (pintype "bidirectional"))
    )
    (net (code "112") (name "unconnected-(IC3-CBUS2-Pad13)") (class "Default")
      (node (ref "IC3") (pin "13") (pinfunction "CBUS2_13") (pintype "bidirectional"))
    )
    (net (code "113") (name "unconnected-(IC3-CBUS3-Pad14)") (class "Default")
      (node (ref "IC3") (pin "14") (pinfunction "CBUS3_14") (pintype "bidirectional"))
    )
    (net (code "114") (name "unconnected-(IC3-CBUS4-Pad12)") (class "Default")
      (node (ref "IC3") (pin "12") (pinfunction "CBUS4_12") (pintype "bidirectional"))
    )
    (net (code "115") (name "unconnected-(IC3-OSCI-Pad27)") (class "Default")
      (node (ref "IC3") (pin "27") (pinfunction "OSCI_27") (pintype "input"))
    )
    (net (code "116") (name "unconnected-(IC3-OSCO-Pad28)") (class "Default")
      (node (ref "IC3") (pin "28") (pinfunction "OSCO_28") (pintype "output"))
    )
    (net (code "117") (name "unconnected-(IC3-TEST-Pad26)") (class "Default")
      (node (ref "IC3") (pin "26") (pinfunction "TEST_26") (pintype "input"))
    )
    (net (code "118") (name "unconnected-(IC3-~{CTS}-Pad11)") (class "Default")
      (node (ref "IC3") (pin "11") (pinfunction "~{CTS}_11") (pintype "input"))
    )
    (net (code "119") (name "unconnected-(IC3-~{DCD}-Pad10)") (class "Default")
      (node (ref "IC3") (pin "10") (pinfunction "~{DCD}_10") (pintype "input"))
    )
    (net (code "120") (name "unconnected-(IC3-~{DSR}-Pad9)") (class "Default")
      (node (ref "IC3") (pin "9") (pinfunction "~{DSR}_9") (pintype "input"))
    )
    (net (code "121") (name "unconnected-(IC3-~{DTR}-Pad2)") (class "Default")
      (node (ref "IC3") (pin "2") (pinfunction "~{DTR}_2") (pintype "output"))
    )
    (net (code "122") (name "unconnected-(IC3-~{RESET}-Pad19)") (class "Default")
      (node (ref "IC3") (pin "19") (pinfunction "~{RESET}_19") (pintype "input"))
    )
    (net (code "123") (name "unconnected-(IC3-~{RI}-Pad6)") (class "Default")
      (node (ref "IC3") (pin "6") (pinfunction "~{RI}_6") (pintype "input"))
    )
    (net (code "124") (name "unconnected-(IC3-~{RTS}-Pad3)") (class "Default")
      (node (ref "IC3") (pin "3") (pinfunction "~{RTS}_3") (pintype "output"))
    )
    (net (code "125") (name "unconnected-(INTERRUPTER_5V-S-Pad3)") (class "Default")
      (node (ref "INTERRUPTER_5V") (pin "3") (pinfunction "S_3") (pintype "passive"))
    )
    (net (code "126") (name "unconnected-(INTERRUPTEUR_SERVOS-S-Pad3)") (class "Default")
      (node (ref "INTERRUPTEUR_SERVOS") (pin "3") (pinfunction "S_3") (pintype "passive"))
    )
    (net (code "127") (name "unconnected-(MINIUSB-PadID)") (class "Default")
      (node (ref "MINIUSB") (pin "ID") (pinfunction "ID_ID") (pintype "passive"))
    )
  )
)
